# IR_module_V0_2.net
KiCad netlist of a schematic drawn in EAGLE
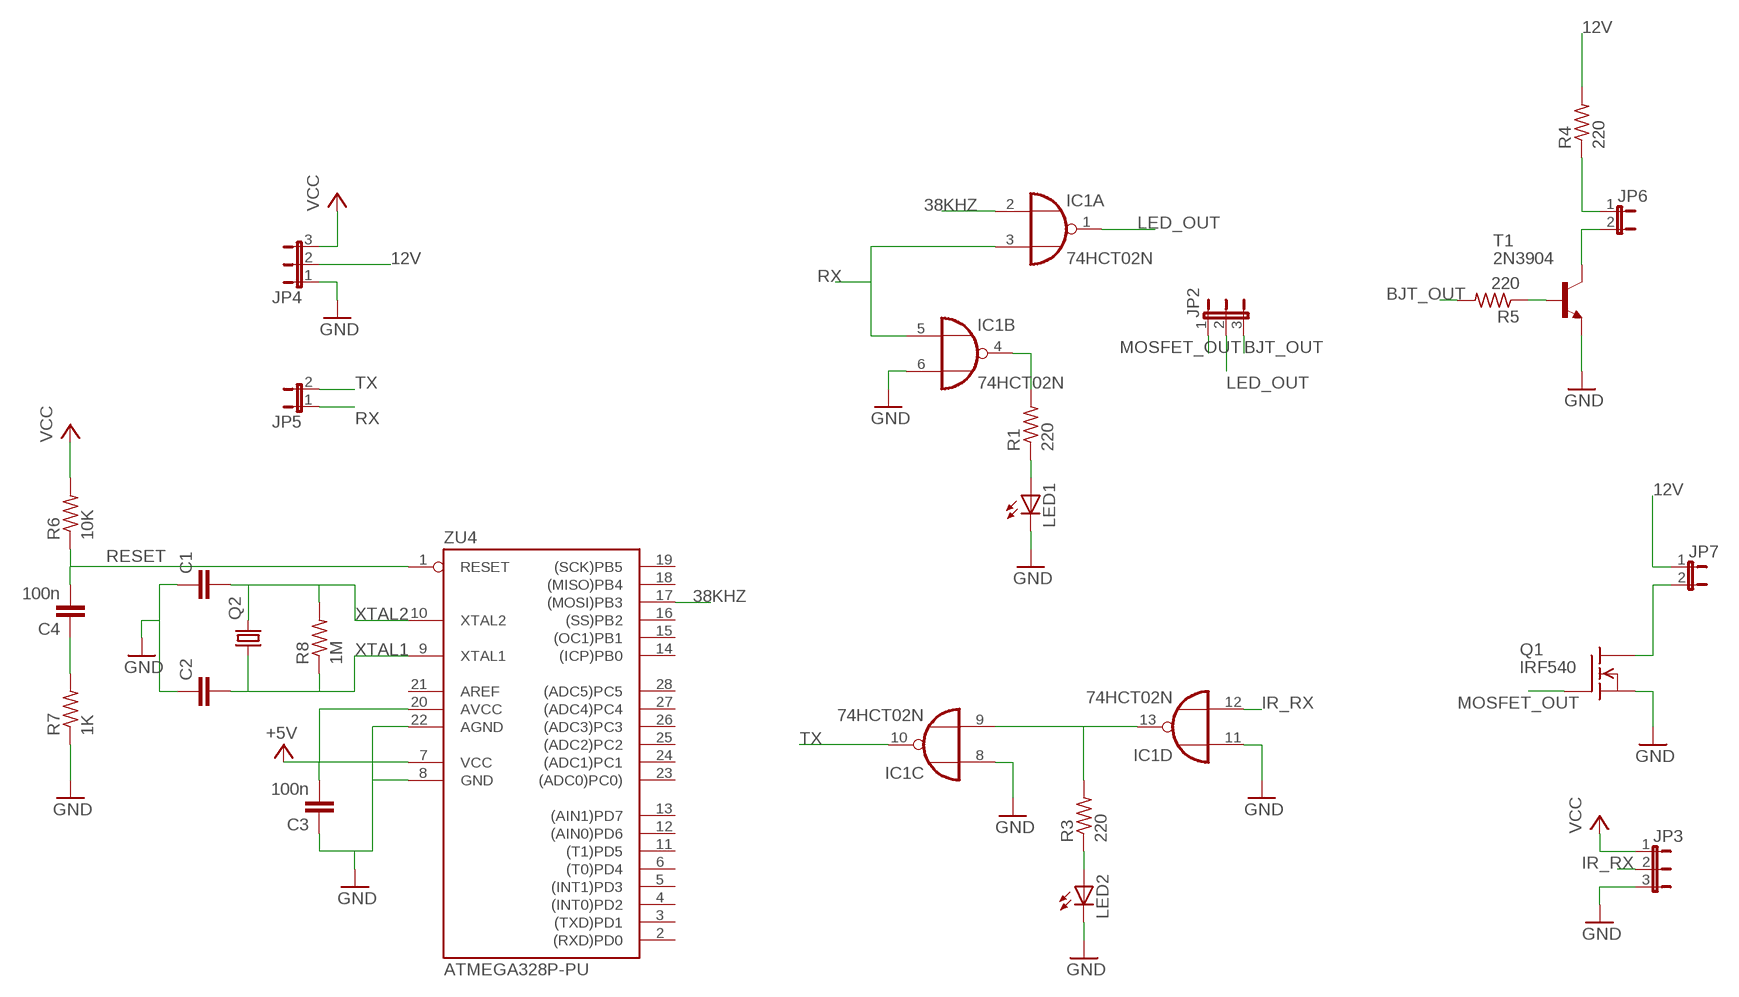
[diagram p0: schematic, sheet 1]

(export (version "E")
  (design (tool "Eeschema 10.0.6"))
  (components
    (comp (ref "C1")
      (value "CAPPTH3")
      (footprint "eagle-import:CAP-PTH-LARGE")
      (libsource (lib "eagle-import") (part "CAPPTH3"))
    )
    (comp (ref "C2")
      (value "CAPPTH3")
      (footprint "eagle-import:CAP-PTH-LARGE")
      (libsource (lib "eagle-import") (part "CAPPTH3"))
    )
    (comp (ref "C3")
      (value "100n")
      (footprint "eagle-import:CAP-PTH-LARGE")
      (libsource (lib "eagle-import") (part "CAPPTH3"))
    )
    (comp (ref "C4")
      (value "100n")
      (footprint "eagle-import:CAP-PTH-LARGE")
      (libsource (lib "eagle-import") (part "CAPPTH3"))
    )
    (comp (ref "IC1")
      (value "74HCT02N")
      (footprint "eagle-import:DIL14")
      (libsource (lib "eagle-import") (part "7402NHCT"))
    )
    (comp (ref "JP2")
      (value "JP2E")
      (footprint "eagle-import:JP2")
      (libsource (lib "eagle-import") (part "JP2E"))
    )
    (comp (ref "JP3")
      (value "JP2W")
      (footprint "eagle-import:JP2W")
      (libsource (lib "eagle-import") (part "JP2W"))
    )
    (comp (ref "JP4")
      (value "JP2E")
      (footprint "eagle-import:JP2")
      (libsource (lib "eagle-import") (part "JP2E"))
    )
    (comp (ref "JP5")
      (value "JP1E")
      (footprint "eagle-import:JP1")
      (libsource (lib "eagle-import") (part "JP1E"))
    )
    (comp (ref "JP6")
      (value "JP1E")
      (footprint "eagle-import:JP1")
      (libsource (lib "eagle-import") (part "JP1E"))
    )
    (comp (ref "JP7")
      (value "JP1E")
      (footprint "eagle-import:JP1")
      (libsource (lib "eagle-import") (part "JP1E"))
    )
    (comp (ref "LED1")
      (value "LED5MM")
      (footprint "eagle-import:LED5MM")
      (libsource (lib "eagle-import") (part "LED5MM"))
    )
    (comp (ref "LED2")
      (value "LED5MM")
      (footprint "eagle-import:LED5MM")
      (libsource (lib "eagle-import") (part "LED5MM"))
    )
    (comp (ref "Q1")
      (value "IRF540")
      (footprint "eagle-import:TO220")
      (libsource (lib "eagle-import") (part "IRF540"))
    )
    (comp (ref "Q2")
      (value "CRYSTALHC49S")
      (footprint "eagle-import:HC49_S")
      (libsource (lib "eagle-import") (part "CRYSTALHC49S"))
    )
    (comp (ref "R1")
      (value "220")
      (footprint "eagle-import:0207_10")
      (libsource (lib "eagle-import") (part "R-US_0207/10"))
    )
    (comp (ref "R3")
      (value "220")
      (footprint "eagle-import:0207_10")
      (libsource (lib "eagle-import") (part "R-US_0207/10"))
    )
    (comp (ref "R4")
      (value "220")
      (footprint "eagle-import:0207_10")
      (libsource (lib "eagle-import") (part "R-US_0207/10"))
    )
    (comp (ref "R5")
      (value "220")
      (footprint "eagle-import:0207_10")
      (libsource (lib "eagle-import") (part "R-US_0207/10"))
    )
    (comp (ref "R6")
      (value "10K")
      (footprint "eagle-import:0207_10")
      (libsource (lib "eagle-import") (part "R-US_0207/10"))
    )
    (comp (ref "R7")
      (value "1K")
      (footprint "eagle-import:0207_10")
      (libsource (lib "eagle-import") (part "R-US_0207/10"))
    )
    (comp (ref "R8")
      (value "1M")
      (footprint "eagle-import:0207_10")
      (libsource (lib "eagle-import") (part "R-US_0207/10"))
    )
    (comp (ref "T1")
      (value "2N3904")
      (footprint "eagle-import:TO92")
      (libsource (lib "eagle-import") (part "2N3904"))
    )
    (comp (ref "ZU4")
      (value "ATMEGA328P-PU")
      (footprint "eagle-import:DIL28-3")
      (libsource (lib "eagle-import") (part "ATMEGA328P-PU"))
    )
  )
  (nets
    (net (code "1") (name "+5V") (class "Default")
      (node (ref "C3") (pin "2") (pinfunction "2_2") (pintype "passive"))
      (node (ref "ZU4") (pin "20") (pinfunction "AVCC_20") (pintype "power_in"))
      (node (ref "ZU4") (pin "7") (pinfunction "VCC_7") (pintype "power_in"))
    )
    (net (code "2") (name "/12V") (class "Default")
      (node (ref "JP4") (pin "2") (pinfunction "2_2") (pintype "passive"))
      (node (ref "JP7") (pin "1") (pinfunction "1_1") (pintype "passive"))
      (node (ref "R4") (pin "2") (pinfunction "2_2") (pintype "passive"))
    )
    (net (code "3") (name "/38KHZ") (class "Default")
      (node (ref "IC1") (pin "2") (pinfunction "I0_2") (pintype "input"))
      (node (ref "ZU4") (pin "17") (pinfunction "(MOSI)PB3_17") (pintype "bidirectional"))
    )
    (net (code "4") (name "/BJT_OUT") (class "Default")
      (node (ref "JP2") (pin "3") (pinfunction "3_3") (pintype "passive"))
      (node (ref "R5") (pin "2") (pinfunction "2_2") (pintype "passive"))
    )
    (net (code "5") (name "/IR_RX") (class "Default")
      (node (ref "IC1") (pin "12") (pinfunction "I1_12") (pintype "input"))
      (node (ref "JP3") (pin "2") (pinfunction "2_2") (pintype "passive"))
    )
    (net (code "6") (name "/LED_OUT") (class "Default")
      (node (ref "IC1") (pin "1") (pinfunction "O_1") (pintype "output"))
      (node (ref "JP2") (pin "2") (pinfunction "2_2") (pintype "passive"))
    )
    (net (code "7") (name "/MOSFET_OUT") (class "Default")
      (node (ref "JP2") (pin "1") (pinfunction "1_1") (pintype "passive"))
      (node (ref "Q1") (pin "1") (pinfunction "G_1") (pintype "passive"))
    )
    (net (code "8") (name "/RESET") (class "Default")
      (node (ref "C4") (pin "2") (pinfunction "2_2") (pintype "passive"))
      (node (ref "R6") (pin "1") (pinfunction "1_1") (pintype "passive"))
      (node (ref "ZU4") (pin "1") (pinfunction "RESET_1") (pintype "input"))
    )
    (net (code "9") (name "/RX") (class "Default")
      (node (ref "IC1") (pin "3") (pinfunction "I1_3") (pintype "input"))
      (node (ref "IC1") (pin "5") (pinfunction "I0_5") (pintype "input"))
      (node (ref "JP5") (pin "1") (pinfunction "1_1") (pintype "passive"))
    )
    (net (code "10") (name "/TX") (class "Default")
      (node (ref "IC1") (pin "10") (pinfunction "O_10") (pintype "output"))
      (node (ref "JP5") (pin "2") (pinfunction "2_2") (pintype "passive"))
    )
    (net (code "11") (name "/XTAL1") (class "Default")
      (node (ref "C2") (pin "2") (pinfunction "2_2") (pintype "passive"))
      (node (ref "Q2") (pin "1") (pinfunction "1_1") (pintype "passive"))
      (node (ref "R8") (pin "1") (pinfunction "1_1") (pintype "passive"))
      (node (ref "ZU4") (pin "9") (pinfunction "XTAL1_9") (pintype "bidirectional"))
    )
    (net (code "12") (name "/XTAL2") (class "Default")
      (node (ref "C1") (pin "2") (pinfunction "2_2") (pintype "passive"))
      (node (ref "Q2") (pin "2") (pinfunction "2_2") (pintype "passive"))
      (node (ref "R8") (pin "2") (pinfunction "2_2") (pintype "passive"))
      (node (ref "ZU4") (pin "10") (pinfunction "XTAL2_10") (pintype "bidirectional"))
    )
    (net (code "13") (name "GND") (class "Default")
      (node (ref "C1") (pin "1") (pinfunction "1_1") (pintype "passive"))
      (node (ref "C2") (pin "1") (pinfunction "1_1") (pintype "passive"))
      (node (ref "C3") (pin "1") (pinfunction "1_1") (pintype "passive"))
      (node (ref "IC1") (pin "11") (pinfunction "I0_11") (pintype "input"))
      (node (ref "IC1") (pin "6") (pinfunction "I1_6") (pintype "input"))
      (node (ref "IC1") (pin "8") (pinfunction "I0_8") (pintype "input"))
      (node (ref "JP3") (pin "3") (pinfunction "3_3") (pintype "passive"))
      (node (ref "JP4") (pin "1") (pinfunction "1_1") (pintype "passive"))
      (node (ref "LED1") (pin "K") (pinfunction "C_K") (pintype "passive"))
      (node (ref "LED2") (pin "K") (pinfunction "C_K") (pintype "passive"))
      (node (ref "Q1") (pin "3") (pinfunction "S_3") (pintype "passive"))
      (node (ref "R7") (pin "1") (pinfunction "1_1") (pintype "passive"))
      (node (ref "T1") (pin "3") (pinfunction "E_3") (pintype "passive"))
      (node (ref "ZU4") (pin "22") (pinfunction "AGND_22") (pintype "power_in"))
      (node (ref "ZU4") (pin "8") (pinfunction "GND_8") (pintype "power_in"))
    )
    (net (code "14") (name "Net-(C4-Pad1)") (class "Default")
      (node (ref "C4") (pin "1") (pinfunction "1_1") (pintype "passive"))
      (node (ref "R7") (pin "2") (pinfunction "2_2") (pintype "passive"))
    )
    (net (code "15") (name "Net-(IC1B-O)") (class "Default")
      (node (ref "IC1") (pin "4") (pinfunction "O_4") (pintype "output"))
      (node (ref "R1") (pin "2") (pinfunction "2_2") (pintype "passive"))
    )
    (net (code "16") (name "Net-(IC1C-I1)") (class "Default")
      (node (ref "IC1") (pin "13") (pinfunction "O_13") (pintype "output"))
      (node (ref "IC1") (pin "9") (pinfunction "I1_9") (pintype "input"))
      (node (ref "R3") (pin "2") (pinfunction "2_2") (pintype "passive"))
    )
    (net (code "17") (name "Net-(JP6-Pad1)") (class "Default")
      (node (ref "JP6") (pin "1") (pinfunction "1_1") (pintype "passive"))
      (node (ref "R4") (pin "1") (pinfunction "1_1") (pintype "passive"))
    )
    (net (code "18") (name "Net-(LED1-PadA)") (class "Default")
      (node (ref "LED1") (pin "A") (pinfunction "A_A") (pintype "passive"))
      (node (ref "R1") (pin "1") (pinfunction "1_1") (pintype "passive"))
    )
    (net (code "19") (name "Net-(LED2-PadA)") (class "Default")
      (node (ref "LED2") (pin "A") (pinfunction "A_A") (pintype "passive"))
      (node (ref "R3") (pin "1") (pinfunction "1_1") (pintype "passive"))
    )
    (net (code "20") (name "Net-(Q1-D)") (class "Default")
      (node (ref "JP7") (pin "2") (pinfunction "2_2") (pintype "passive"))
      (node (ref "Q1") (pin "2") (pinfunction "D_2") (pintype "passive"))
    )
    (net (code "21") (name "Net-(T1-B)") (class "Default")
      (node (ref "R5") (pin "1") (pinfunction "1_1") (pintype "passive"))
      (node (ref "T1") (pin "2") (pinfunction "B_2") (pintype "passive"))
    )
    (net (code "22") (name "Net-(T1-C)") (class "Default")
      (node (ref "JP6") (pin "2") (pinfunction "2_2") (pintype "passive"))
      (node (ref "T1") (pin "1") (pinfunction "C_1") (pintype "passive"))
    )
    (net (code "23") (name "VCC") (class "Default")
      (node (ref "JP3") (pin "1") (pinfunction "1_1") (pintype "passive"))
      (node (ref "JP4") (pin "3") (pinfunction "3_3") (pintype "passive"))
      (node (ref "R6") (pin "2") (pinfunction "2_2") (pintype "passive"))
    )
    (net (code "24") (name "unconnected-(ZU4-(ADC0)PC0)-Pad23)") (class "Default")
      (node (ref "ZU4") (pin "23") (pinfunction "(ADC0)PC0)_23") (pintype "bidirectional"))
    )
    (net (code "25") (name "unconnected-(ZU4-(ADC1)PC1-Pad24)") (class "Default")
      (node (ref "ZU4") (pin "24") (pinfunction "(ADC1)PC1_24") (pintype "bidirectional"))
    )
    (net (code "26") (name "unconnected-(ZU4-(ADC2)PC2-Pad25)") (class "Default")
      (node (ref "ZU4") (pin "25") (pinfunction "(ADC2)PC2_25") (pintype "bidirectional"))
    )
    (net (code "27") (name "unconnected-(ZU4-(ADC3)PC3-Pad26)") (class "Default")
      (node (ref "ZU4") (pin "26") (pinfunction "(ADC3)PC3_26") (pintype "bidirectional"))
    )
    (net (code "28") (name "unconnected-(ZU4-(ADC4)PC4-Pad27)") (class "Default")
      (node (ref "ZU4") (pin "27") (pinfunction "(ADC4)PC4_27") (pintype "bidirectional"))
    )
    (net (code "29") (name "unconnected-(ZU4-(ADC5)PC5-Pad28)") (class "Default")
      (node (ref "ZU4") (pin "28") (pinfunction "(ADC5)PC5_28") (pintype "bidirectional"))
    )
    (net (code "30") (name "unconnected-(ZU4-(AIN0)PD6-Pad12)") (class "Default")
      (node (ref "ZU4") (pin "12") (pinfunction "(AIN0)PD6_12") (pintype "bidirectional"))
    )
    (net (code "31") (name "unconnected-(ZU4-(AIN1)PD7-Pad13)") (class "Default")
      (node (ref "ZU4") (pin "13") (pinfunction "(AIN1)PD7_13") (pintype "bidirectional"))
    )
    (net (code "32") (name "unconnected-(ZU4-(ICP)PB0-Pad14)") (class "Default")
      (node (ref "ZU4") (pin "14") (pinfunction "(ICP)PB0_14") (pintype "bidirectional"))
    )
    (net (code "33") (name "unconnected-(ZU4-(INT0)PD2-Pad4)") (class "Default")
      (node (ref "ZU4") (pin "4") (pinfunction "(INT0)PD2_4") (pintype "bidirectional"))
    )
    (net (code "34") (name "unconnected-(ZU4-(INT1)PD3-Pad5)") (class "Default")
      (node (ref "ZU4") (pin "5") (pinfunction "(INT1)PD3_5") (pintype "bidirectional"))
    )
    (net (code "35") (name "unconnected-(ZU4-(MISO)PB4-Pad18)") (class "Default")
      (node (ref "ZU4") (pin "18") (pinfunction "(MISO)PB4_18") (pintype "bidirectional"))
    )
    (net (code "36") (name "unconnected-(ZU4-(OC1)PB1-Pad15)") (class "Default")
      (node (ref "ZU4") (pin "15") (pinfunction "(OC1)PB1_15") (pintype "bidirectional"))
    )
    (net (code "37") (name "unconnected-(ZU4-(RXD)PD0-Pad2)") (class "Default")
      (node (ref "ZU4") (pin "2") (pinfunction "(RXD)PD0_2") (pintype "bidirectional"))
    )
    (net (code "38") (name "unconnected-(ZU4-(SCK)PB5-Pad19)") (class "Default")
      (node (ref "ZU4") (pin "19") (pinfunction "(SCK)PB5_19") (pintype "bidirectional"))
    )
    (net (code "39") (name "unconnected-(ZU4-(SS)PB2-Pad16)") (class "Default")
      (node (ref "ZU4") (pin "16") (pinfunction "(SS)PB2_16") (pintype "bidirectional"))
    )
    (net (code "40") (name "unconnected-(ZU4-(T0)PD4-Pad6)") (class "Default")
      (node (ref "ZU4") (pin "6") (pinfunction "(T0)PD4_6") (pintype "bidirectional"))
    )
    (net (code "41") (name "unconnected-(ZU4-(T1)PD5-Pad11)") (class "Default")
      (node (ref "ZU4") (pin "11") (pinfunction "(T1)PD5_11") (pintype "bidirectional"))
    )
    (net (code "42") (name "unconnected-(ZU4-(TXD)PD1-Pad3)") (class "Default")
      (node (ref "ZU4") (pin "3") (pinfunction "(TXD)PD1_3") (pintype "bidirectional"))
    )
    (net (code "43") (name "unconnected-(ZU4-AREF-Pad21)") (class "Default")
      (node (ref "ZU4") (pin "21") (pinfunction "AREF_21") (pintype "passive"))
    )
  )
)
